# imu.net
KiCad netlist of a schematic drawn in Altium Designer
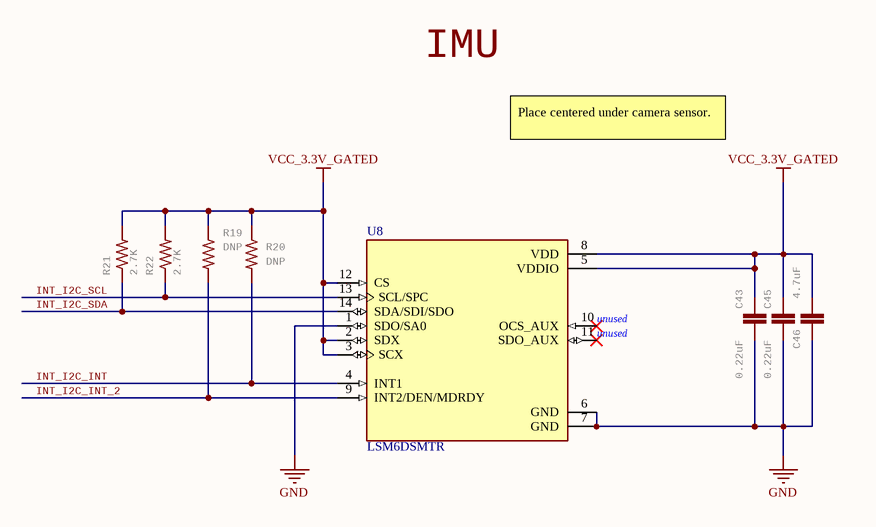
[diagram p0: imu.SchDoc]

(export (version "E")
  (design (tool "Eeschema 10.0.6"))
  (components
    (comp (ref "C43")
      (value "0.22uF")
      (footprint "C0201")
      (description "CAPACITOR, European symbol")
      (fields (field (name "MPN") "GRM033R60J224ME15D"))
      (libsource (lib "rt10") (part "C-EUC0201"))
    )
    (comp (ref "C45")
      (value "0.22uF")
      (footprint "C0201")
      (description "CAPACITOR, European symbol")
      (fields (field (name "MPN") "GRM033R60J224ME15D"))
      (libsource (lib "rt10") (part "C-EUC0201"))
    )
    (comp (ref "C46")
      (value "4.7uF")
      (footprint "0402-CAP")
      (description "CapacitorStandard 0603 ceramic capacitor, and 0.1\" leaded capacitor.")
      (fields (field (name "MPN") "JMK105BBJ475MV-F"))
      (libsource (lib "rt10") (part "CAP0402-CAP"))
    )
    (comp (ref "R19")
      (value "DNP")
      (footprint "0402-RES")
      (description "ResistorBasic schematic elements and footprints for 0603, 1206, and PTH resistors.")
      (libsource (lib "rt10") (part "RESISTOR0402-RES"))
    )
    (comp (ref "R20")
      (value "DNP")
      (footprint "0402-RES")
      (description "ResistorBasic schematic elements and footprints for 0603, 1206, and PTH resistors.")
      (libsource (lib "rt10") (part "RESISTOR0402-RES"))
    )
    (comp (ref "R21")
      (value "2.7K")
      (footprint "0402-RES")
      (description "ResistorBasic schematic elements and footprints for 0603, 1206, and PTH resistors.")
      (fields (field (name "MPN") "AC0402JR-072K7L"))
      (libsource (lib "rt10") (part "RESISTOR0402-RES"))
    )
    (comp (ref "R22")
      (value "2.7K")
      (footprint "0402-RES")
      (description "ResistorBasic schematic elements and footprints for 0603, 1206, and PTH resistors.")
      (fields (field (name "MPN") "AC0402JR-072K7L"))
      (libsource (lib "rt10") (part "RESISTOR0402-RES"))
    )
    (comp (ref "U8")
      (value "LSM6DSMTR")
      (footprint "LSM6DSMTR")
      (description "Accelerometer, Gyroscope, Temperature, 6 Axis Sensor IÂ²C, SPI Output")
      (fields (field (name "MF") "STMicroelectronics"))
      (libsource (lib "stm32n657") (part "LSM6DSMTR"))
    )
  )
  (nets
    (net (code "1") (name "/INT_I2C_INT") (class "Default")
      (node (ref "R20") (pin "2") (pinfunction "2_2") (pintype "passive"))
      (node (ref "U8") (pin "4") (pinfunction "INT1_4") (pintype "input"))
    )
    (net (code "2") (name "/INT_I2C_INT_2") (class "Default")
      (node (ref "R19") (pin "2") (pinfunction "2_2") (pintype "passive"))
      (node (ref "U8") (pin "9") (pinfunction "INT2/DEN/MDRDY_9") (pintype "input"))
    )
    (net (code "3") (name "/INT_I2C_SCL") (class "Default")
      (node (ref "R22") (pin "1") (pinfunction "1_1") (pintype "passive"))
      (node (ref "U8") (pin "13") (pinfunction "SCL/SPC_13") (pintype "input"))
    )
    (net (code "4") (name "/INT_I2C_SDA") (class "Default")
      (node (ref "R21") (pin "1") (pinfunction "1_1") (pintype "passive"))
      (node (ref "U8") (pin "14") (pinfunction "SDA/SDI/SDO_14") (pintype "bidirectional"))
    )
    (net (code "5") (name "GND") (class "Default")
      (node (ref "C43") (pin "2") (pinfunction "2_2") (pintype "passive"))
      (node (ref "C45") (pin "2") (pinfunction "2_2") (pintype "passive"))
      (node (ref "C46") (pin "1") (pinfunction "1_1") (pintype "passive"))
      (node (ref "U8") (pin "1") (pinfunction "SDO/SA0_1") (pintype "bidirectional"))
      (node (ref "U8") (pin "6") (pinfunction "GND_6") (pintype "power_in"))
      (node (ref "U8") (pin "7") (pinfunction "GND_7") (pintype "power_in"))
    )
    (net (code "6") (name "VCC_3.3V_GATED") (class "Default")
      (node (ref "C43") (pin "1") (pinfunction "1_1") (pintype "passive"))
      (node (ref "C45") (pin "1") (pinfunction "1_1") (pintype "passive"))
      (node (ref "C46") (pin "2") (pinfunction "2_2") (pintype "passive"))
      (node (ref "R19") (pin "1") (pinfunction "1_1") (pintype "passive"))
      (node (ref "R20") (pin "1") (pinfunction "1_1") (pintype "passive"))
      (node (ref "R21") (pin "2") (pinfunction "2_2") (pintype "passive"))
      (node (ref "R22") (pin "2") (pinfunction "2_2") (pintype "passive"))
      (node (ref "U8") (pin "12") (pinfunction "CS_12") (pintype "input"))
      (node (ref "U8") (pin "2") (pinfunction "SDX_2") (pintype "bidirectional"))
      (node (ref "U8") (pin "3") (pinfunction "SCX_3") (pintype "bidirectional"))
      (node (ref "U8") (pin "5") (pinfunction "VDDIO_5") (pintype "power_in"))
      (node (ref "U8") (pin "8") (pinfunction "VDD_8") (pintype "power_in"))
    )
    (net (code "7") (name "unconnected-(U8-OCS_AUX-Pad10)") (class "Default")
      (node (ref "U8") (pin "10") (pinfunction "OCS_AUX_10") (pintype "input+no_connect"))
    )
    (net (code "8") (name "unconnected-(U8-SDO_AUX-Pad11)") (class "Default")
      (node (ref "U8") (pin "11") (pinfunction "SDO_AUX_11") (pintype "bidirectional+no_connect"))
    )
  )
)
